# edges_expander_v01.net
KiCad netlist of a schematic drawn in EAGLE
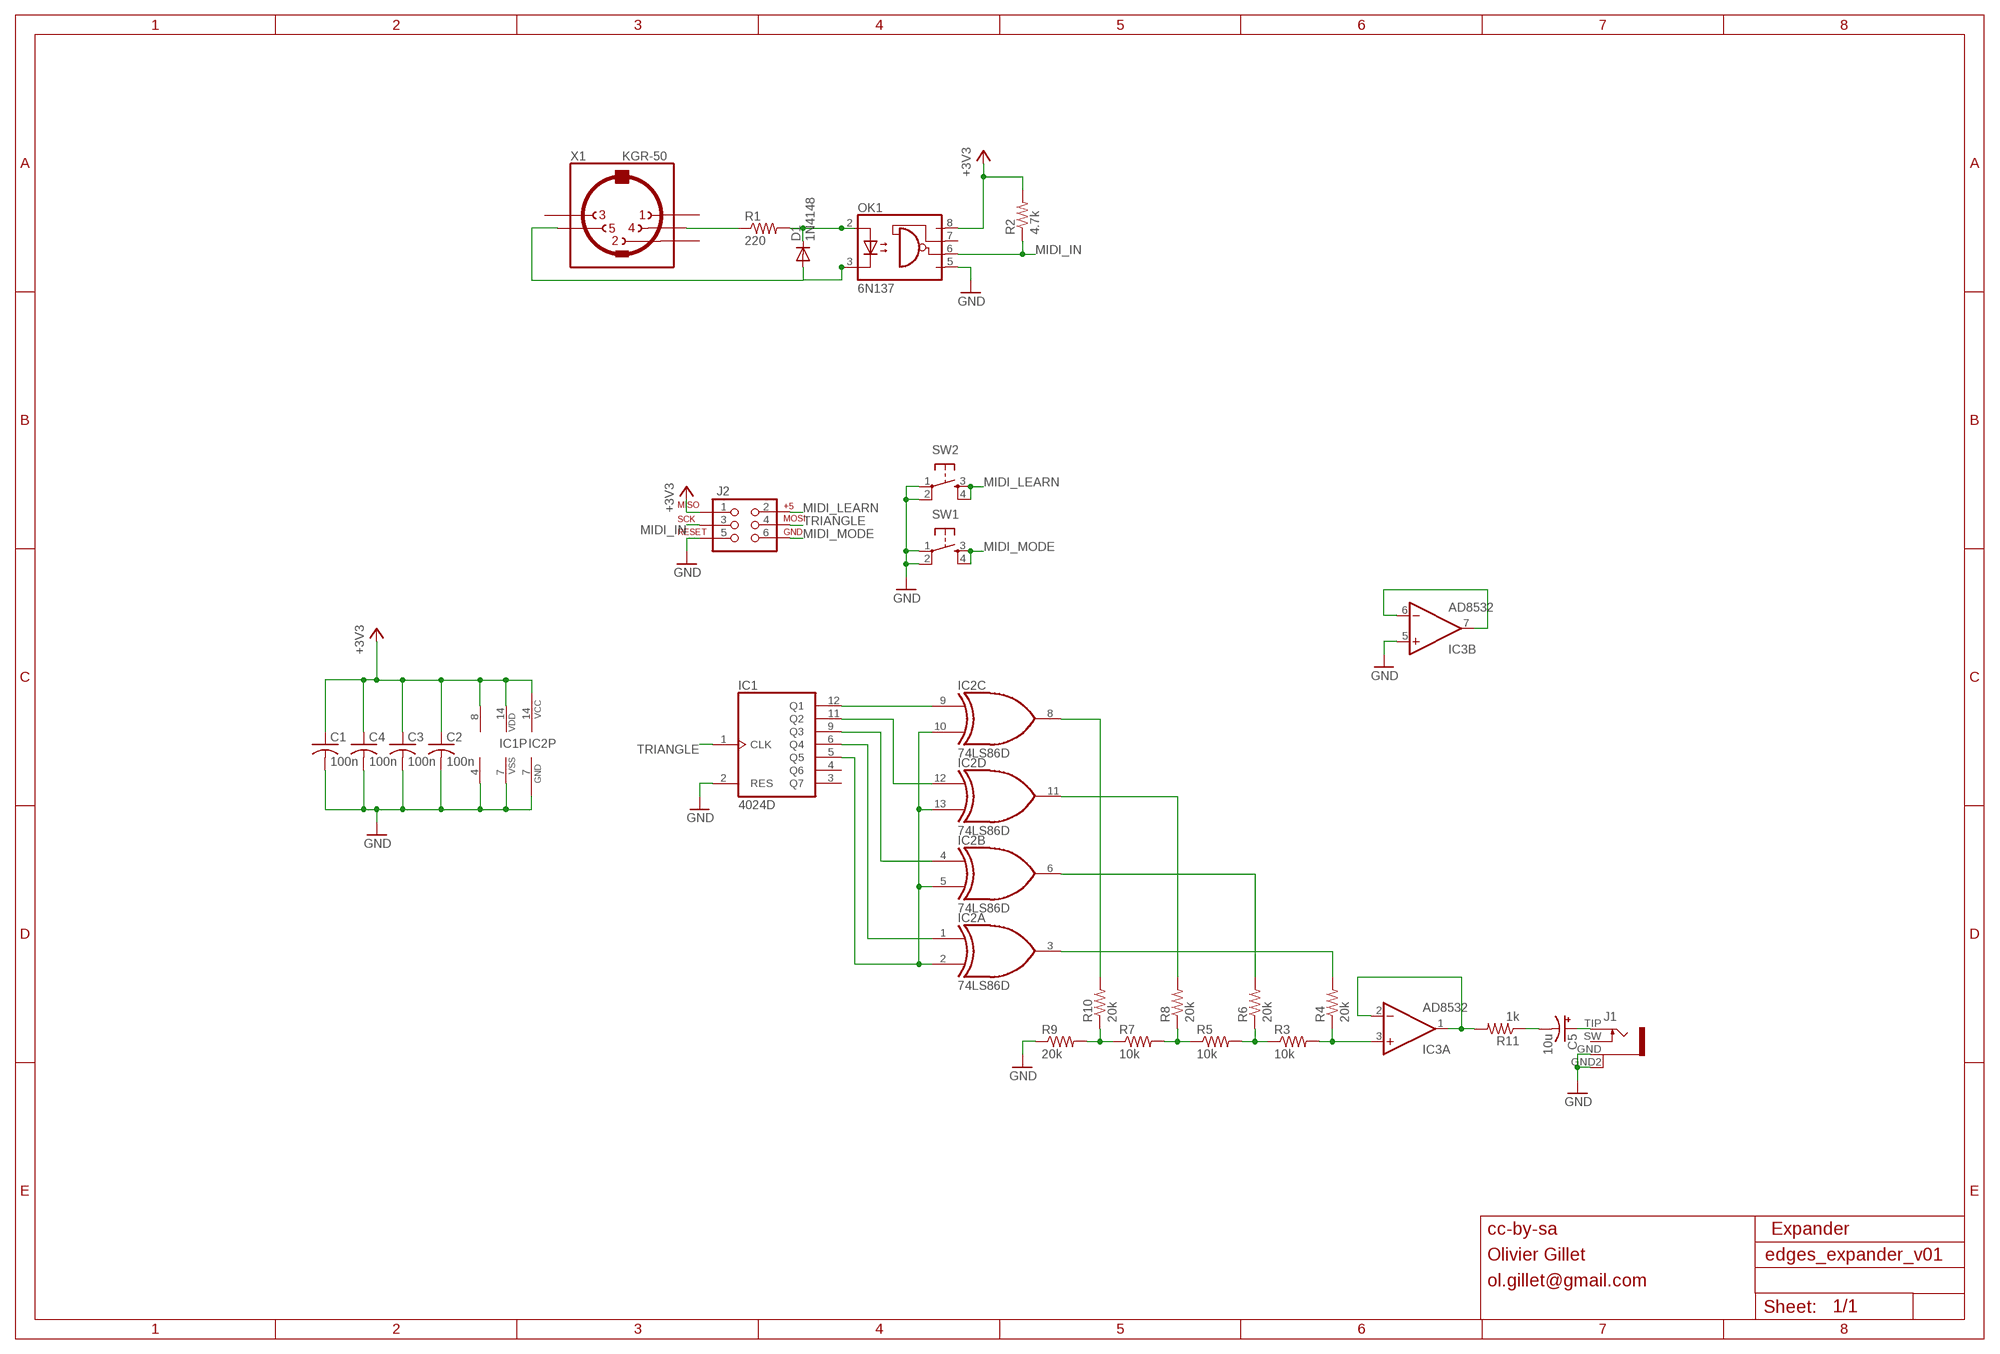
[diagram p0: schematic, sheet 1]

(export (version "E")
  (design (tool "Eeschema 10.0.6"))
  (components
    (comp (ref "C1")
      (value "100n")
      (footprint "eagle-import:C0603")
      (libsource (lib "eagle-import") (part "C-USC0603"))
    )
    (comp (ref "C2")
      (value "100n")
      (footprint "eagle-import:C0603")
      (libsource (lib "eagle-import") (part "C-USC0603"))
    )
    (comp (ref "C3")
      (value "100n")
      (footprint "eagle-import:C0603")
      (libsource (lib "eagle-import") (part "C-USC0603"))
    )
    (comp (ref "C4")
      (value "100n")
      (footprint "eagle-import:C0603")
      (libsource (lib "eagle-import") (part "C-USC0603"))
    )
    (comp (ref "C5")
      (value "10u")
      (footprint "eagle-import:PANASONIC_B")
      (libsource (lib "eagle-import") (part "CPOL-USB"))
    )
    (comp (ref "D1")
      (value "1N4148")
      (footprint "eagle-import:SOD323-W")
      (libsource (lib "eagle-import") (part "DIODE-SOD323-W"))
    )
    (comp (ref "IC1")
      (value "4024D")
      (footprint "eagle-import:SO14")
      (libsource (lib "eagle-import") (part "4024D"))
    )
    (comp (ref "IC2")
      (value "74LS86D")
      (footprint "eagle-import:SO14")
      (libsource (lib "eagle-import") (part "7486DLS"))
    )
    (comp (ref "IC3")
      (value "AD8532")
      (footprint "eagle-import:SO08")
      (libsource (lib "eagle-import") (part "TL072D"))
    )
    (comp (ref "J1")
      (value "PJ301WQP")
      (footprint "eagle-import:WQP_PJ_301BM")
      (libsource (lib "eagle-import") (part "PJ301WQP"))
    )
    (comp (ref "J2")
      (value "AVR_SPI_PRG_6PTH")
      (footprint "eagle-import:2X3")
      (libsource (lib "eagle-import") (part "AVR_SPI_PRG_6PTH"))
    )
    (comp (ref "OK1")
      (value "6N137")
      (footprint "eagle-import:DIL8-SMD")
      (libsource (lib "eagle-import") (part "6N137SMT"))
    )
    (comp (ref "R1")
      (value "220")
      (footprint "eagle-import:R0603")
      (libsource (lib "eagle-import") (part "R-US_R0603"))
    )
    (comp (ref "R2")
      (value "4.7k")
      (footprint "eagle-import:R0603")
      (libsource (lib "eagle-import") (part "R-US_R0603"))
    )
    (comp (ref "R3")
      (value "10k")
      (footprint "eagle-import:R0603")
      (libsource (lib "eagle-import") (part "R-US_R0603"))
    )
    (comp (ref "R4")
      (value "20k")
      (footprint "eagle-import:R0603")
      (libsource (lib "eagle-import") (part "R-US_R0603"))
    )
    (comp (ref "R5")
      (value "10k")
      (footprint "eagle-import:R0603")
      (libsource (lib "eagle-import") (part "R-US_R0603"))
    )
    (comp (ref "R6")
      (value "20k")
      (footprint "eagle-import:R0603")
      (libsource (lib "eagle-import") (part "R-US_R0603"))
    )
    (comp (ref "R7")
      (value "10k")
      (footprint "eagle-import:R0603")
      (libsource (lib "eagle-import") (part "R-US_R0603"))
    )
    (comp (ref "R8")
      (value "20k")
      (footprint "eagle-import:R0603")
      (libsource (lib "eagle-import") (part "R-US_R0603"))
    )
    (comp (ref "R9")
      (value "20k")
      (footprint "eagle-import:R0603")
      (libsource (lib "eagle-import") (part "R-US_R0603"))
    )
    (comp (ref "R10")
      (value "20k")
      (footprint "eagle-import:R0603")
      (libsource (lib "eagle-import") (part "R-US_R0603"))
    )
    (comp (ref "R11")
      (value "1k")
      (footprint "eagle-import:R0603")
      (libsource (lib "eagle-import") (part "R-US_R0603"))
    )
    (comp (ref "SW1")
      (value "TAC_SWITCHPTH")
      (footprint "eagle-import:TACTILE-PTH")
      (libsource (lib "eagle-import") (part "TAC_SWITCHPTH"))
    )
    (comp (ref "SW2")
      (value "TAC_SWITCHPTH")
      (footprint "eagle-import:TACTILE-PTH")
      (libsource (lib "eagle-import") (part "TAC_SWITCHPTH"))
    )
    (comp (ref "X1")
      (value "KGR-50")
      (footprint "eagle-import:KGR-50")
      (libsource (lib "eagle-import") (part "KGR-50"))
    )
  )
  (nets
    (net (code "1") (name "+3V3") (class "Default")
      (node (ref "C1") (pin "1") (pinfunction "1_1") (pintype "passive"))
      (node (ref "C2") (pin "1") (pinfunction "1_1") (pintype "passive"))
      (node (ref "C3") (pin "1") (pinfunction "1_1") (pintype "passive"))
      (node (ref "C4") (pin "1") (pinfunction "1_1") (pintype "passive"))
      (node (ref "IC1") (pin "14") (pinfunction "VDD_14") (pintype "power_in"))
      (node (ref "IC2") (pin "14") (pinfunction "VCC_14") (pintype "power_in"))
      (node (ref "IC3") (pin "8") (pinfunction "V+_8") (pintype "power_in"))
      (node (ref "J2") (pin "1") (pinfunction "1_1") (pintype "passive"))
      (node (ref "OK1") (pin "8") (pinfunction "VCC_8") (pintype "passive"))
      (node (ref "R2") (pin "2") (pinfunction "2_2") (pintype "passive"))
    )
    (net (code "2") (name "/MIDI_IN") (class "Default")
      (node (ref "J2") (pin "3") (pinfunction "3_3") (pintype "passive"))
      (node (ref "OK1") (pin "6") (pinfunction "VO_6") (pintype "passive"))
      (node (ref "R2") (pin "1") (pinfunction "1_1") (pintype "passive"))
    )
    (net (code "3") (name "/MIDI_LEARN") (class "Default")
      (node (ref "J2") (pin "2") (pinfunction "2_2") (pintype "passive"))
      (node (ref "SW2") (pin "3") (pinfunction "3_3") (pintype "passive"))
      (node (ref "SW2") (pin "4") (pinfunction "4_4") (pintype "passive"))
    )
    (net (code "4") (name "/MIDI_MODE") (class "Default")
      (node (ref "J2") (pin "6") (pinfunction "6_6") (pintype "passive"))
      (node (ref "SW1") (pin "3") (pinfunction "3_3") (pintype "passive"))
      (node (ref "SW1") (pin "4") (pinfunction "4_4") (pintype "passive"))
    )
    (net (code "5") (name "/TRIANGLE") (class "Default")
      (node (ref "IC1") (pin "1") (pinfunction "CLK_1") (pintype "input"))
      (node (ref "J2") (pin "4") (pinfunction "4_4") (pintype "passive"))
    )
    (net (code "6") (name "GND") (class "Default")
      (node (ref "C1") (pin "2") (pinfunction "2_2") (pintype "passive"))
      (node (ref "C2") (pin "2") (pinfunction "2_2") (pintype "passive"))
      (node (ref "C3") (pin "2") (pinfunction "2_2") (pintype "passive"))
      (node (ref "C4") (pin "2") (pinfunction "2_2") (pintype "passive"))
      (node (ref "IC1") (pin "2") (pinfunction "RES_2") (pintype "input"))
      (node (ref "IC1") (pin "7") (pinfunction "VSS_7") (pintype "power_in"))
      (node (ref "IC2") (pin "7") (pinfunction "GND_7") (pintype "power_in"))
      (node (ref "IC3") (pin "4") (pinfunction "V-_4") (pintype "power_in"))
      (node (ref "IC3") (pin "5") (pinfunction "+IN_5") (pintype "input"))
      (node (ref "J1") (pin "GND") (pinfunction "1_GND") (pintype "passive"))
      (node (ref "J1") (pin "GND2") (pinfunction "4_GND2") (pintype "passive"))
      (node (ref "J2") (pin "5") (pinfunction "5_5") (pintype "passive"))
      (node (ref "OK1") (pin "5") (pinfunction "GND_5") (pintype "passive"))
      (node (ref "R9") (pin "1") (pinfunction "1_1") (pintype "passive"))
      (node (ref "SW1") (pin "1") (pinfunction "1_1") (pintype "passive"))
      (node (ref "SW1") (pin "2") (pinfunction "2_2") (pintype "passive"))
      (node (ref "SW2") (pin "1") (pinfunction "1_1") (pintype "passive"))
      (node (ref "SW2") (pin "2") (pinfunction "2_2") (pintype "passive"))
    )
    (net (code "7") (name "Net-(C5-Pad-)") (class "Default")
      (node (ref "C5") (pin "-") (pinfunction "-_-") (pintype "passive"))
      (node (ref "R11") (pin "1") (pinfunction "1_1") (pintype "passive"))
    )
    (net (code "8") (name "Net-(IC1A-Q1)") (class "Default")
      (node (ref "IC1") (pin "12") (pinfunction "Q1_12") (pintype "output"))
      (node (ref "IC2") (pin "9") (pinfunction "I0_9") (pintype "input"))
    )
    (net (code "9") (name "Net-(IC1A-Q2)") (class "Default")
      (node (ref "IC1") (pin "11") (pinfunction "Q2_11") (pintype "output"))
      (node (ref "IC2") (pin "12") (pinfunction "I0_12") (pintype "input"))
    )
    (net (code "10") (name "Net-(IC1A-Q3)") (class "Default")
      (node (ref "IC1") (pin "9") (pinfunction "Q3_9") (pintype "output"))
      (node (ref "IC2") (pin "4") (pinfunction "I0_4") (pintype "input"))
    )
    (net (code "11") (name "Net-(IC1A-Q4)") (class "Default")
      (node (ref "IC1") (pin "6") (pinfunction "Q4_6") (pintype "output"))
      (node (ref "IC2") (pin "1") (pinfunction "I0_1") (pintype "input"))
    )
    (net (code "12") (name "Net-(IC1A-Q5)") (class "Default")
      (node (ref "IC1") (pin "5") (pinfunction "Q5_5") (pintype "output"))
      (node (ref "IC2") (pin "10") (pinfunction "I1_10") (pintype "input"))
      (node (ref "IC2") (pin "13") (pinfunction "I1_13") (pintype "input"))
      (node (ref "IC2") (pin "2") (pinfunction "I1_2") (pintype "input"))
      (node (ref "IC2") (pin "5") (pinfunction "I1_5") (pintype "input"))
    )
    (net (code "13") (name "Net-(IC2A-O)") (class "Default")
      (node (ref "IC2") (pin "3") (pinfunction "O_3") (pintype "output"))
      (node (ref "R4") (pin "2") (pinfunction "2_2") (pintype "passive"))
    )
    (net (code "14") (name "Net-(IC2B-O)") (class "Default")
      (node (ref "IC2") (pin "6") (pinfunction "O_6") (pintype "output"))
      (node (ref "R6") (pin "2") (pinfunction "2_2") (pintype "passive"))
    )
    (net (code "15") (name "Net-(IC2C-O)") (class "Default")
      (node (ref "IC2") (pin "8") (pinfunction "O_8") (pintype "output"))
      (node (ref "R10") (pin "2") (pinfunction "2_2") (pintype "passive"))
    )
    (net (code "16") (name "Net-(IC2D-O)") (class "Default")
      (node (ref "IC2") (pin "11") (pinfunction "O_11") (pintype "output"))
      (node (ref "R8") (pin "2") (pinfunction "2_2") (pintype "passive"))
    )
    (net (code "17") (name "Net-(IC3A-+IN)") (class "Default")
      (node (ref "IC3") (pin "3") (pinfunction "+IN_3") (pintype "input"))
      (node (ref "R3") (pin "2") (pinfunction "2_2") (pintype "passive"))
      (node (ref "R4") (pin "1") (pinfunction "1_1") (pintype "passive"))
    )
    (net (code "18") (name "Net-(IC3A--IN)") (class "Default")
      (node (ref "IC3") (pin "1") (pinfunction "OUT_1") (pintype "output"))
      (node (ref "IC3") (pin "2") (pinfunction "-IN_2") (pintype "input"))
      (node (ref "R11") (pin "2") (pinfunction "2_2") (pintype "passive"))
    )
    (net (code "19") (name "Net-(IC3B--IN)") (class "Default")
      (node (ref "IC3") (pin "6") (pinfunction "-IN_6") (pintype "input"))
      (node (ref "IC3") (pin "7") (pinfunction "OUT_7") (pintype "output"))
    )
    (net (code "20") (name "Net-(J1-2)") (class "Default")
      (node (ref "C5") (pin "+") (pinfunction "+_+") (pintype "passive"))
      (node (ref "J1") (pin "TIP") (pinfunction "2_TIP") (pintype "passive"))
    )
    (net (code "21") (name "Net-(OK1-A)") (class "Default")
      (node (ref "D1") (pin "C") (pinfunction "C_C") (pintype "passive"))
      (node (ref "OK1") (pin "2") (pinfunction "A_2") (pintype "passive"))
      (node (ref "R1") (pin "2") (pinfunction "2_2") (pintype "passive"))
    )
    (net (code "22") (name "Net-(OK1-C)") (class "Default")
      (node (ref "D1") (pin "A") (pinfunction "A_A") (pintype "passive"))
      (node (ref "OK1") (pin "3") (pinfunction "C_3") (pintype "passive"))
      (node (ref "X1") (pin "P$5") (pinfunction "5_P$5") (pintype "bidirectional"))
    )
    (net (code "23") (name "Net-(R3-Pad1)") (class "Default")
      (node (ref "R3") (pin "1") (pinfunction "1_1") (pintype "passive"))
      (node (ref "R5") (pin "2") (pinfunction "2_2") (pintype "passive"))
      (node (ref "R6") (pin "1") (pinfunction "1_1") (pintype "passive"))
    )
    (net (code "24") (name "Net-(R5-Pad1)") (class "Default")
      (node (ref "R5") (pin "1") (pinfunction "1_1") (pintype "passive"))
      (node (ref "R7") (pin "2") (pinfunction "2_2") (pintype "passive"))
      (node (ref "R8") (pin "1") (pinfunction "1_1") (pintype "passive"))
    )
    (net (code "25") (name "Net-(R10-Pad1)") (class "Default")
      (node (ref "R10") (pin "1") (pinfunction "1_1") (pintype "passive"))
      (node (ref "R7") (pin "1") (pinfunction "1_1") (pintype "passive"))
      (node (ref "R9") (pin "2") (pinfunction "2_2") (pintype "passive"))
    )
    (net (code "26") (name "Net-(X1-4)") (class "Default")
      (node (ref "R1") (pin "1") (pinfunction "1_1") (pintype "passive"))
      (node (ref "X1") (pin "P$4") (pinfunction "4_P$4") (pintype "bidirectional"))
    )
    (net (code "27") (name "unconnected-(IC1A-Q6-Pad4)") (class "Default")
      (node (ref "IC1") (pin "4") (pinfunction "Q6_4") (pintype "output"))
    )
    (net (code "28") (name "unconnected-(IC1A-Q7-Pad3)") (class "Default")
      (node (ref "IC1") (pin "3") (pinfunction "Q7_3") (pintype "output"))
    )
    (net (code "29") (name "unconnected-(J1-3-PadSW)") (class "Default")
      (node (ref "J1") (pin "SW") (pinfunction "3_SW") (pintype "passive"))
    )
    (net (code "30") (name "unconnected-(OK1-VE-Pad7)") (class "Default")
      (node (ref "OK1") (pin "7") (pinfunction "VE_7") (pintype "passive"))
    )
    (net (code "31") (name "unconnected-(X1-1-PadP$1)") (class "Default")
      (node (ref "X1") (pin "P$1") (pinfunction "1_P$1") (pintype "no_connect"))
    )
    (net (code "32") (name "unconnected-(X1-2-PadP$2)") (class "Default")
      (node (ref "X1") (pin "P$2") (pinfunction "2_P$2") (pintype "no_connect"))
    )
    (net (code "33") (name "unconnected-(X1-3-PadP$3)") (class "Default")
      (node (ref "X1") (pin "P$3") (pinfunction "3_P$3") (pintype "no_connect"))
    )
  )
)
